# Keyboard.net
KiCad netlist of a schematic drawn in EAGLE
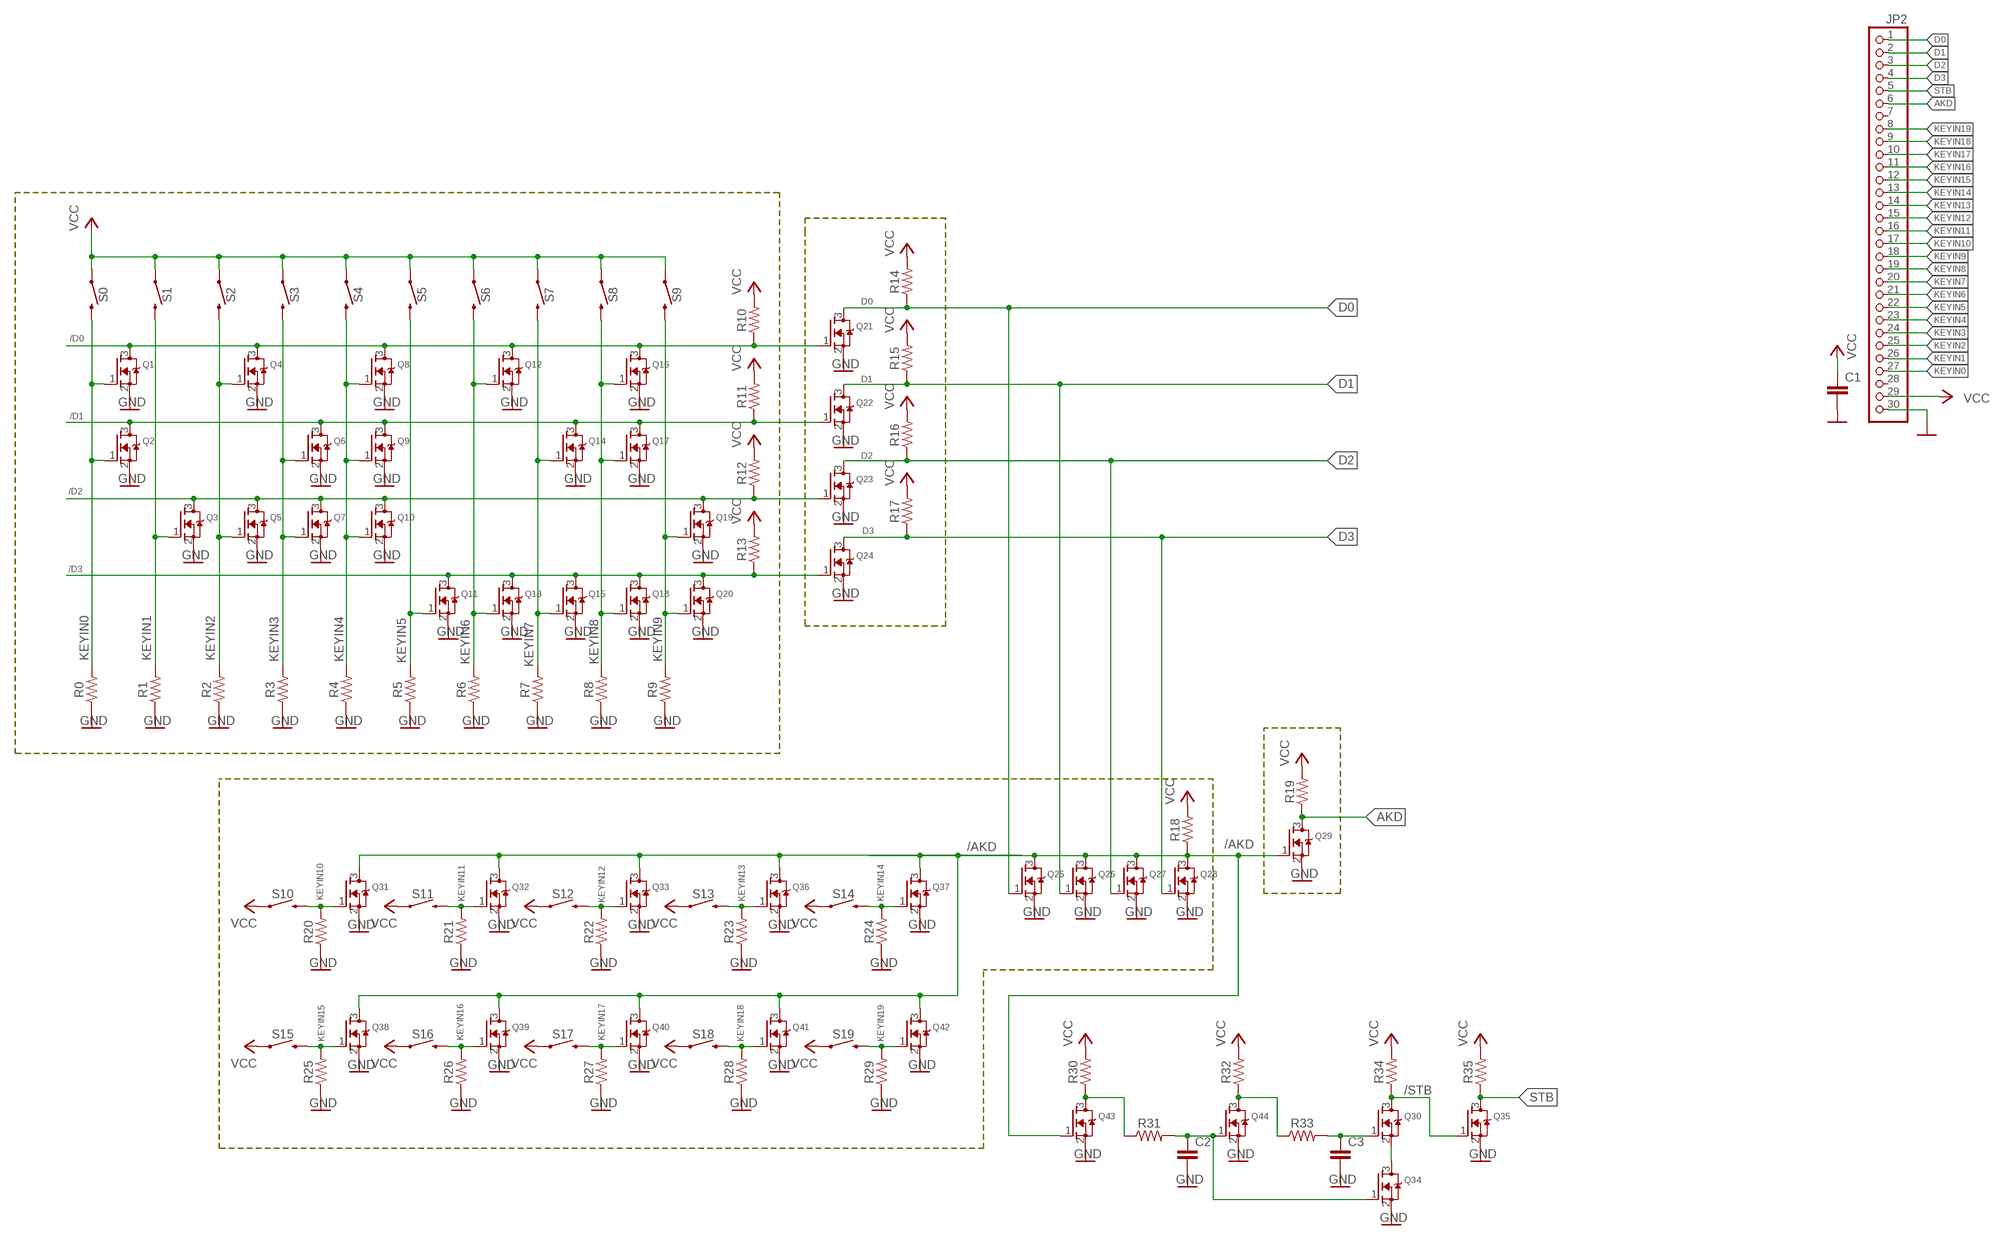
[diagram p0: schematic, sheet 1]

(export (version "E")
  (design (tool "Eeschema 10.0.6"))
  (components
    (comp (ref "C1")
      (value "C-EUC0805K")
      (footprint "eagle-import:C0805K")
      (libsource (lib "eagle-import") (part "C-EUC0805K"))
    )
    (comp (ref "C2")
      (value "C-EUC0805K")
      (footprint "eagle-import:C0805K")
      (libsource (lib "eagle-import") (part "C-EUC0805K"))
    )
    (comp (ref "C3")
      (value "C-EUC0805K")
      (footprint "eagle-import:C0805K")
      (libsource (lib "eagle-import") (part "C-EUC0805K"))
    )
    (comp (ref "JP2")
      (value "PINHD-1X30")
      (footprint "eagle-import:1X30")
      (libsource (lib "eagle-import") (part "PINHD-1X30"))
    )
    (comp (ref "Q1")
      (value "NMOSREFLOW")
      (footprint "eagle-import:SOT23")
      (libsource (lib "eagle-import") (part "NMOSREFLOW"))
    )
    (comp (ref "Q2")
      (value "NMOSREFLOW")
      (footprint "eagle-import:SOT23")
      (libsource (lib "eagle-import") (part "NMOSREFLOW"))
    )
    (comp (ref "Q3")
      (value "NMOSREFLOW")
      (footprint "eagle-import:SOT23")
      (libsource (lib "eagle-import") (part "NMOSREFLOW"))
    )
    (comp (ref "Q4")
      (value "NMOSREFLOW")
      (footprint "eagle-import:SOT23")
      (libsource (lib "eagle-import") (part "NMOSREFLOW"))
    )
    (comp (ref "Q5")
      (value "NMOSREFLOW")
      (footprint "eagle-import:SOT23")
      (libsource (lib "eagle-import") (part "NMOSREFLOW"))
    )
    (comp (ref "Q6")
      (value "NMOSREFLOW")
      (footprint "eagle-import:SOT23")
      (libsource (lib "eagle-import") (part "NMOSREFLOW"))
    )
    (comp (ref "Q7")
      (value "NMOSREFLOW")
      (footprint "eagle-import:SOT23")
      (libsource (lib "eagle-import") (part "NMOSREFLOW"))
    )
    (comp (ref "Q8")
      (value "NMOSREFLOW")
      (footprint "eagle-import:SOT23")
      (libsource (lib "eagle-import") (part "NMOSREFLOW"))
    )
    (comp (ref "Q9")
      (value "NMOSREFLOW")
      (footprint "eagle-import:SOT23")
      (libsource (lib "eagle-import") (part "NMOSREFLOW"))
    )
    (comp (ref "Q10")
      (value "NMOSREFLOW")
      (footprint "eagle-import:SOT23")
      (libsource (lib "eagle-import") (part "NMOSREFLOW"))
    )
    (comp (ref "Q11")
      (value "NMOSREFLOW")
      (footprint "eagle-import:SOT23")
      (libsource (lib "eagle-import") (part "NMOSREFLOW"))
    )
    (comp (ref "Q12")
      (value "NMOSREFLOW")
      (footprint "eagle-import:SOT23")
      (libsource (lib "eagle-import") (part "NMOSREFLOW"))
    )
    (comp (ref "Q13")
      (value "NMOSREFLOW")
      (footprint "eagle-import:SOT23")
      (libsource (lib "eagle-import") (part "NMOSREFLOW"))
    )
    (comp (ref "Q14")
      (value "NMOSREFLOW")
      (footprint "eagle-import:SOT23")
      (libsource (lib "eagle-import") (part "NMOSREFLOW"))
    )
    (comp (ref "Q15")
      (value "NMOSREFLOW")
      (footprint "eagle-import:SOT23")
      (libsource (lib "eagle-import") (part "NMOSREFLOW"))
    )
    (comp (ref "Q16")
      (value "NMOSREFLOW")
      (footprint "eagle-import:SOT23")
      (libsource (lib "eagle-import") (part "NMOSREFLOW"))
    )
    (comp (ref "Q17")
      (value "NMOSREFLOW")
      (footprint "eagle-import:SOT23")
      (libsource (lib "eagle-import") (part "NMOSREFLOW"))
    )
    (comp (ref "Q18")
      (value "NMOSREFLOW")
      (footprint "eagle-import:SOT23")
      (libsource (lib "eagle-import") (part "NMOSREFLOW"))
    )
    (comp (ref "Q19")
      (value "NMOSREFLOW")
      (footprint "eagle-import:SOT23")
      (libsource (lib "eagle-import") (part "NMOSREFLOW"))
    )
    (comp (ref "Q20")
      (value "NMOSREFLOW")
      (footprint "eagle-import:SOT23")
      (libsource (lib "eagle-import") (part "NMOSREFLOW"))
    )
    (comp (ref "Q21")
      (value "NMOSREFLOW")
      (footprint "eagle-import:SOT23")
      (libsource (lib "eagle-import") (part "NMOSREFLOW"))
    )
    (comp (ref "Q22")
      (value "NMOSREFLOW")
      (footprint "eagle-import:SOT23")
      (libsource (lib "eagle-import") (part "NMOSREFLOW"))
    )
    (comp (ref "Q23")
      (value "NMOSREFLOW")
      (footprint "eagle-import:SOT23")
      (libsource (lib "eagle-import") (part "NMOSREFLOW"))
    )
    (comp (ref "Q24")
      (value "NMOSREFLOW")
      (footprint "eagle-import:SOT23")
      (libsource (lib "eagle-import") (part "NMOSREFLOW"))
    )
    (comp (ref "Q25")
      (value "NMOSREFLOW")
      (footprint "eagle-import:SOT23")
      (libsource (lib "eagle-import") (part "NMOSREFLOW"))
    )
    (comp (ref "Q26")
      (value "NMOSREFLOW")
      (footprint "eagle-import:SOT23")
      (libsource (lib "eagle-import") (part "NMOSREFLOW"))
    )
    (comp (ref "Q27")
      (value "NMOSREFLOW")
      (footprint "eagle-import:SOT23")
      (libsource (lib "eagle-import") (part "NMOSREFLOW"))
    )
    (comp (ref "Q28")
      (value "NMOSREFLOW")
      (footprint "eagle-import:SOT23")
      (libsource (lib "eagle-import") (part "NMOSREFLOW"))
    )
    (comp (ref "Q29")
      (value "NMOSREFLOW")
      (footprint "eagle-import:SOT23")
      (libsource (lib "eagle-import") (part "NMOSREFLOW"))
    )
    (comp (ref "Q30")
      (value "NMOSREFLOW")
      (footprint "eagle-import:SOT23")
      (libsource (lib "eagle-import") (part "NMOSREFLOW"))
    )
    (comp (ref "Q31")
      (value "NMOSREFLOW")
      (footprint "eagle-import:SOT23")
      (libsource (lib "eagle-import") (part "NMOSREFLOW"))
    )
    (comp (ref "Q32")
      (value "NMOSREFLOW")
      (footprint "eagle-import:SOT23")
      (libsource (lib "eagle-import") (part "NMOSREFLOW"))
    )
    (comp (ref "Q33")
      (value "NMOSREFLOW")
      (footprint "eagle-import:SOT23")
      (libsource (lib "eagle-import") (part "NMOSREFLOW"))
    )
    (comp (ref "Q34")
      (value "NMOSREFLOW")
      (footprint "eagle-import:SOT23")
      (libsource (lib "eagle-import") (part "NMOSREFLOW"))
    )
    (comp (ref "Q35")
      (value "NMOSREFLOW")
      (footprint "eagle-import:SOT23")
      (libsource (lib "eagle-import") (part "NMOSREFLOW"))
    )
    (comp (ref "Q36")
      (value "NMOSREFLOW")
      (footprint "eagle-import:SOT23")
      (libsource (lib "eagle-import") (part "NMOSREFLOW"))
    )
    (comp (ref "Q37")
      (value "NMOSREFLOW")
      (footprint "eagle-import:SOT23")
      (libsource (lib "eagle-import") (part "NMOSREFLOW"))
    )
    (comp (ref "Q38")
      (value "NMOSREFLOW")
      (footprint "eagle-import:SOT23")
      (libsource (lib "eagle-import") (part "NMOSREFLOW"))
    )
    (comp (ref "Q39")
      (value "NMOSREFLOW")
      (footprint "eagle-import:SOT23")
      (libsource (lib "eagle-import") (part "NMOSREFLOW"))
    )
    (comp (ref "Q40")
      (value "NMOSREFLOW")
      (footprint "eagle-import:SOT23")
      (libsource (lib "eagle-import") (part "NMOSREFLOW"))
    )
    (comp (ref "Q41")
      (value "NMOSREFLOW")
      (footprint "eagle-import:SOT23")
      (libsource (lib "eagle-import") (part "NMOSREFLOW"))
    )
    (comp (ref "Q42")
      (value "NMOSREFLOW")
      (footprint "eagle-import:SOT23")
      (libsource (lib "eagle-import") (part "NMOSREFLOW"))
    )
    (comp (ref "Q43")
      (value "NMOSREFLOW")
      (footprint "eagle-import:SOT23")
      (libsource (lib "eagle-import") (part "NMOSREFLOW"))
    )
    (comp (ref "Q44")
      (value "NMOSREFLOW")
      (footprint "eagle-import:SOT23")
      (libsource (lib "eagle-import") (part "NMOSREFLOW"))
    )
    (comp (ref "R0")
      (value "RESISTOR0805")
      (footprint "eagle-import:0805")
      (libsource (lib "eagle-import") (part "RESISTOR0805"))
    )
    (comp (ref "R1")
      (value "RESISTOR0805")
      (footprint "eagle-import:0805")
      (libsource (lib "eagle-import") (part "RESISTOR0805"))
    )
    (comp (ref "R2")
      (value "RESISTOR0805")
      (footprint "eagle-import:0805")
      (libsource (lib "eagle-import") (part "RESISTOR0805"))
    )
    (comp (ref "R3")
      (value "RESISTOR0805")
      (footprint "eagle-import:0805")
      (libsource (lib "eagle-import") (part "RESISTOR0805"))
    )
    (comp (ref "R4")
      (value "RESISTOR0805")
      (footprint "eagle-import:0805")
      (libsource (lib "eagle-import") (part "RESISTOR0805"))
    )
    (comp (ref "R5")
      (value "RESISTOR0805")
      (footprint "eagle-import:0805")
      (libsource (lib "eagle-import") (part "RESISTOR0805"))
    )
    (comp (ref "R6")
      (value "RESISTOR0805")
      (footprint "eagle-import:0805")
      (libsource (lib "eagle-import") (part "RESISTOR0805"))
    )
    (comp (ref "R7")
      (value "RESISTOR0805")
      (footprint "eagle-import:0805")
      (libsource (lib "eagle-import") (part "RESISTOR0805"))
    )
    (comp (ref "R8")
      (value "RESISTOR0805")
      (footprint "eagle-import:0805")
      (libsource (lib "eagle-import") (part "RESISTOR0805"))
    )
    (comp (ref "R9")
      (value "RESISTOR0805")
      (footprint "eagle-import:0805")
      (libsource (lib "eagle-import") (part "RESISTOR0805"))
    )
    (comp (ref "R10")
      (value "RESISTOR0805")
      (footprint "eagle-import:0805")
      (libsource (lib "eagle-import") (part "RESISTOR0805"))
    )
    (comp (ref "R11")
      (value "RESISTOR0805")
      (footprint "eagle-import:0805")
      (libsource (lib "eagle-import") (part "RESISTOR0805"))
    )
    (comp (ref "R12")
      (value "RESISTOR0805")
      (footprint "eagle-import:0805")
      (libsource (lib "eagle-import") (part "RESISTOR0805"))
    )
    (comp (ref "R13")
      (value "RESISTOR0805")
      (footprint "eagle-import:0805")
      (libsource (lib "eagle-import") (part "RESISTOR0805"))
    )
    (comp (ref "R14")
      (value "RESISTOR0805")
      (footprint "eagle-import:0805")
      (libsource (lib "eagle-import") (part "RESISTOR0805"))
    )
    (comp (ref "R15")
      (value "RESISTOR0805")
      (footprint "eagle-import:0805")
      (libsource (lib "eagle-import") (part "RESISTOR0805"))
    )
    (comp (ref "R16")
      (value "RESISTOR0805")
      (footprint "eagle-import:0805")
      (libsource (lib "eagle-import") (part "RESISTOR0805"))
    )
    (comp (ref "R17")
      (value "RESISTOR0805")
      (footprint "eagle-import:0805")
      (libsource (lib "eagle-import") (part "RESISTOR0805"))
    )
    (comp (ref "R18")
      (value "RESISTOR0805")
      (footprint "eagle-import:0805")
      (libsource (lib "eagle-import") (part "RESISTOR0805"))
    )
    (comp (ref "R19")
      (value "RESISTOR0805")
      (footprint "eagle-import:0805")
      (libsource (lib "eagle-import") (part "RESISTOR0805"))
    )
    (comp (ref "R20")
      (value "RESISTOR0805")
      (footprint "eagle-import:0805")
      (libsource (lib "eagle-import") (part "RESISTOR0805"))
    )
    (comp (ref "R21")
      (value "RESISTOR0805")
      (footprint "eagle-import:0805")
      (libsource (lib "eagle-import") (part "RESISTOR0805"))
    )
    (comp (ref "R22")
      (value "RESISTOR0805")
      (footprint "eagle-import:0805")
      (libsource (lib "eagle-import") (part "RESISTOR0805"))
    )
    (comp (ref "R23")
      (value "RESISTOR0805")
      (footprint "eagle-import:0805")
      (libsource (lib "eagle-import") (part "RESISTOR0805"))
    )
    (comp (ref "R24")
      (value "RESISTOR0805")
      (footprint "eagle-import:0805")
      (libsource (lib "eagle-import") (part "RESISTOR0805"))
    )
    (comp (ref "R25")
      (value "RESISTOR0805")
      (footprint "eagle-import:0805")
      (libsource (lib "eagle-import") (part "RESISTOR0805"))
    )
    (comp (ref "R26")
      (value "RESISTOR0805")
      (footprint "eagle-import:0805")
      (libsource (lib "eagle-import") (part "RESISTOR0805"))
    )
    (comp (ref "R27")
      (value "RESISTOR0805")
      (footprint "eagle-import:0805")
      (libsource (lib "eagle-import") (part "RESISTOR0805"))
    )
    (comp (ref "R28")
      (value "RESISTOR0805")
      (footprint "eagle-import:0805")
      (libsource (lib "eagle-import") (part "RESISTOR0805"))
    )
    (comp (ref "R29")
      (value "RESISTOR0805")
      (footprint "eagle-import:0805")
      (libsource (lib "eagle-import") (part "RESISTOR0805"))
    )
    (comp (ref "R30")
      (value "RESISTOR0805")
      (footprint "eagle-import:0805")
      (libsource (lib "eagle-import") (part "RESISTOR0805"))
    )
    (comp (ref "R31")
      (value "RESISTOR0805")
      (footprint "eagle-import:0805")
      (libsource (lib "eagle-import") (part "RESISTOR0805"))
    )
    (comp (ref "R32")
      (value "RESISTOR0805")
      (footprint "eagle-import:0805")
      (libsource (lib "eagle-import") (part "RESISTOR0805"))
    )
    (comp (ref "R33")
      (value "RESISTOR0805")
      (footprint "eagle-import:0805")
      (libsource (lib "eagle-import") (part "RESISTOR0805"))
    )
    (comp (ref "R34")
      (value "RESISTOR0805")
      (footprint "eagle-import:0805")
      (libsource (lib "eagle-import") (part "RESISTOR0805"))
    )
    (comp (ref "R35")
      (value "RESISTOR0805")
      (footprint "eagle-import:0805")
      (libsource (lib "eagle-import") (part "RESISTOR0805"))
    )
    (comp (ref "S0")
      (value "MOMENTARY-SWITCH-SPST-PTH-6.0MM")
      (footprint "eagle-import:TACTILE_SWITCH_PTH_6.0MM")
      (libsource (lib "eagle-import") (part "MOMENTARY-SWITCH-SPST-PTH-6.0MM"))
    )
    (comp (ref "S1")
      (value "MOMENTARY-SWITCH-SPST-PTH-6.0MM")
      (footprint "eagle-import:TACTILE_SWITCH_PTH_6.0MM")
      (libsource (lib "eagle-import") (part "MOMENTARY-SWITCH-SPST-PTH-6.0MM"))
    )
    (comp (ref "S2")
      (value "MOMENTARY-SWITCH-SPST-PTH-6.0MM")
      (footprint "eagle-import:TACTILE_SWITCH_PTH_6.0MM")
      (libsource (lib "eagle-import") (part "MOMENTARY-SWITCH-SPST-PTH-6.0MM"))
    )
    (comp (ref "S3")
      (value "MOMENTARY-SWITCH-SPST-PTH-6.0MM")
      (footprint "eagle-import:TACTILE_SWITCH_PTH_6.0MM")
      (libsource (lib "eagle-import") (part "MOMENTARY-SWITCH-SPST-PTH-6.0MM"))
    )
    (comp (ref "S4")
      (value "MOMENTARY-SWITCH-SPST-PTH-6.0MM")
      (footprint "eagle-import:TACTILE_SWITCH_PTH_6.0MM")
      (libsource (lib "eagle-import") (part "MOMENTARY-SWITCH-SPST-PTH-6.0MM"))
    )
    (comp (ref "S5")
      (value "MOMENTARY-SWITCH-SPST-PTH-6.0MM")
      (footprint "eagle-import:TACTILE_SWITCH_PTH_6.0MM")
      (libsource (lib "eagle-import") (part "MOMENTARY-SWITCH-SPST-PTH-6.0MM"))
    )
    (comp (ref "S6")
      (value "MOMENTARY-SWITCH-SPST-PTH-6.0MM")
      (footprint "eagle-import:TACTILE_SWITCH_PTH_6.0MM")
      (libsource (lib "eagle-import") (part "MOMENTARY-SWITCH-SPST-PTH-6.0MM"))
    )
    (comp (ref "S7")
      (value "MOMENTARY-SWITCH-SPST-PTH-6.0MM")
      (footprint "eagle-import:TACTILE_SWITCH_PTH_6.0MM")
      (libsource (lib "eagle-import") (part "MOMENTARY-SWITCH-SPST-PTH-6.0MM"))
    )
    (comp (ref "S8")
      (value "MOMENTARY-SWITCH-SPST-PTH-6.0MM")
      (footprint "eagle-import:TACTILE_SWITCH_PTH_6.0MM")
      (libsource (lib "eagle-import") (part "MOMENTARY-SWITCH-SPST-PTH-6.0MM"))
    )
    (comp (ref "S9")
      (value "MOMENTARY-SWITCH-SPST-PTH-6.0MM")
      (footprint "eagle-import:TACTILE_SWITCH_PTH_6.0MM")
      (libsource (lib "eagle-import") (part "MOMENTARY-SWITCH-SPST-PTH-6.0MM"))
    )
    (comp (ref "S10")
      (value "MOMENTARY-SWITCH-SPST-PTH-6.0MM")
      (footprint "eagle-import:TACTILE_SWITCH_PTH_6.0MM")
      (libsource (lib "eagle-import") (part "MOMENTARY-SWITCH-SPST-PTH-6.0MM"))
    )
    (comp (ref "S11")
      (value "MOMENTARY-SWITCH-SPST-PTH-6.0MM")
      (footprint "eagle-import:TACTILE_SWITCH_PTH_6.0MM")
      (libsource (lib "eagle-import") (part "MOMENTARY-SWITCH-SPST-PTH-6.0MM"))
    )
    (comp (ref "S12")
      (value "MOMENTARY-SWITCH-SPST-PTH-6.0MM")
      (footprint "eagle-import:TACTILE_SWITCH_PTH_6.0MM")
      (libsource (lib "eagle-import") (part "MOMENTARY-SWITCH-SPST-PTH-6.0MM"))
    )
    (comp (ref "S13")
      (value "MOMENTARY-SWITCH-SPST-PTH-6.0MM")
      (footprint "eagle-import:TACTILE_SWITCH_PTH_6.0MM")
      (libsource (lib "eagle-import") (part "MOMENTARY-SWITCH-SPST-PTH-6.0MM"))
    )
    (comp (ref "S14")
      (value "MOMENTARY-SWITCH-SPST-PTH-6.0MM")
      (footprint "eagle-import:TACTILE_SWITCH_PTH_6.0MM")
      (libsource (lib "eagle-import") (part "MOMENTARY-SWITCH-SPST-PTH-6.0MM"))
    )
    (comp (ref "S15")
      (value "MOMENTARY-SWITCH-SPST-PTH-6.0MM")
      (footprint "eagle-import:TACTILE_SWITCH_PTH_6.0MM")
      (libsource (lib "eagle-import") (part "MOMENTARY-SWITCH-SPST-PTH-6.0MM"))
    )
    (comp (ref "S16")
      (value "MOMENTARY-SWITCH-SPST-PTH-6.0MM")
      (footprint "eagle-import:TACTILE_SWITCH_PTH_6.0MM")
      (libsource (lib "eagle-import") (part "MOMENTARY-SWITCH-SPST-PTH-6.0MM"))
    )
    (comp (ref "S17")
      (value "MOMENTARY-SWITCH-SPST-PTH-6.0MM")
      (footprint "eagle-import:TACTILE_SWITCH_PTH_6.0MM")
      (libsource (lib "eagle-import") (part "MOMENTARY-SWITCH-SPST-PTH-6.0MM"))
    )
    (comp (ref "S18")
      (value "MOMENTARY-SWITCH-SPST-PTH-6.0MM")
      (footprint "eagle-import:TACTILE_SWITCH_PTH_6.0MM")
      (libsource (lib "eagle-import") (part "MOMENTARY-SWITCH-SPST-PTH-6.0MM"))
    )
    (comp (ref "S19")
      (value "MOMENTARY-SWITCH-SPST-PTH-6.0MM")
      (footprint "eagle-import:TACTILE_SWITCH_PTH_6.0MM")
      (libsource (lib "eagle-import") (part "MOMENTARY-SWITCH-SPST-PTH-6.0MM"))
    )
  )
  (nets
    (net (code "1") (name "/{slash}AKD") (class "Default")
      (node (ref "Q25") (pin "3") (pinfunction "D_3") (pintype "bidirectional"))
      (node (ref "Q26") (pin "3") (pinfunction "D_3") (pintype "bidirectional"))
      (node (ref "Q27") (pin "3") (pinfunction "D_3") (pintype "bidirectional"))
      (node (ref "Q28") (pin "3") (pinfunction "D_3") (pintype "bidirectional"))
      (node (ref "Q29") (pin "1") (pinfunction "G_1") (pintype "bidirectional"))
      (node (ref "Q31") (pin "3") (pinfunction "D_3") (pintype "bidirectional"))
      (node (ref "Q32") (pin "3") (pinfunction "D_3") (pintype "bidirectional"))
      (node (ref "Q33") (pin "3") (pinfunction "D_3") (pintype "bidirectional"))
      (node (ref "Q36") (pin "3") (pinfunction "D_3") (pintype "bidirectional"))
      (node (ref "Q37") (pin "3") (pinfunction "D_3") (pintype "bidirectional"))
      (node (ref "Q38") (pin "3") (pinfunction "D_3") (pintype "bidirectional"))
      (node (ref "Q39") (pin "3") (pinfunction "D_3") (pintype "bidirectional"))
      (node (ref "Q40") (pin "3") (pinfunction "D_3") (pintype "bidirectional"))
      (node (ref "Q41") (pin "3") (pinfunction "D_3") (pintype "bidirectional"))
      (node (ref "Q42") (pin "3") (pinfunction "D_3") (pintype "bidirectional"))
      (node (ref "Q43") (pin "1") (pinfunction "G_1") (pintype "bidirectional"))
      (node (ref "R18") (pin "1") (pinfunction "1_1") (pintype "passive"))
    )
    (net (code "2") (name "/{slash}D0") (class "Default")
      (node (ref "Q1") (pin "3") (pinfunction "D_3") (pintype "bidirectional"))
      (node (ref "Q12") (pin "3") (pinfunction "D_3") (pintype "bidirectional"))
      (node (ref "Q16") (pin "3") (pinfunction "D_3") (pintype "bidirectional"))
      (node (ref "Q21") (pin "1") (pinfunction "G_1") (pintype "bidirectional"))
      (node (ref "Q4") (pin "3") (pinfunction "D_3") (pintype "bidirectional"))
      (node (ref "Q8") (pin "3") (pinfunction "D_3") (pintype "bidirectional"))
      (node (ref "R10") (pin "1") (pinfunction "1_1") (pintype "passive"))
    )
    (net (code "3") (name "/{slash}D1") (class "Default")
      (node (ref "Q14") (pin "3") (pinfunction "D_3") (pintype "bidirectional"))
      (node (ref "Q17") (pin "3") (pinfunction "D_3") (pintype "bidirectional"))
      (node (ref "Q2") (pin "3") (pinfunction "D_3") (pintype "bidirectional"))
      (node (ref "Q22") (pin "1") (pinfunction "G_1") (pintype "bidirectional"))
      (node (ref "Q6") (pin "3") (pinfunction "D_3") (pintype "bidirectional"))
      (node (ref "Q9") (pin "3") (pinfunction "D_3") (pintype "bidirectional"))
      (node (ref "R11") (pin "1") (pinfunction "1_1") (pintype "passive"))
    )
    (net (code "4") (name "/{slash}D2") (class "Default")
      (node (ref "Q10") (pin "3") (pinfunction "D_3") (pintype "bidirectional"))
      (node (ref "Q19") (pin "3") (pinfunction "D_3") (pintype "bidirectional"))
      (node (ref "Q23") (pin "1") (pinfunction "G_1") (pintype "bidirectional"))
      (node (ref "Q3") (pin "3") (pinfunction "D_3") (pintype "bidirectional"))
      (node (ref "Q5") (pin "3") (pinfunction "D_3") (pintype "bidirectional"))
      (node (ref "Q7") (pin "3") (pinfunction "D_3") (pintype "bidirectional"))
      (node (ref "R12") (pin "1") (pinfunction "1_1") (pintype "passive"))
    )
    (net (code "5") (name "/{slash}D3") (class "Default")
      (node (ref "Q11") (pin "3") (pinfunction "D_3") (pintype "bidirectional"))
      (node (ref "Q13") (pin "3") (pinfunction "D_3") (pintype "bidirectional"))
      (node (ref "Q15") (pin "3") (pinfunction "D_3") (pintype "bidirectional"))
      (node (ref "Q18") (pin "3") (pinfunction "D_3") (pintype "bidirectional"))
      (node (ref "Q20") (pin "3") (pinfunction "D_3") (pintype "bidirectional"))
      (node (ref "Q24") (pin "1") (pinfunction "G_1") (pintype "bidirectional"))
      (node (ref "R13") (pin "1") (pinfunction "1_1") (pintype "passive"))
    )
    (net (code "6") (name "/{slash}STB") (class "Default")
      (node (ref "Q30") (pin "3") (pinfunction "D_3") (pintype "bidirectional"))
      (node (ref "Q35") (pin "1") (pinfunction "G_1") (pintype "bidirectional"))
      (node (ref "R34") (pin "1") (pinfunction "1_1") (pintype "passive"))
    )
    (net (code "7") (name "AKD") (class "Default")
      (node (ref "JP2") (pin "6") (pinfunction "6_6") (pintype "passive"))
      (node (ref "Q29") (pin "3") (pinfunction "D_3") (pintype "bidirectional"))
      (node (ref "R19") (pin "1") (pinfunction "1_1") (pintype "passive"))
    )
    (net (code "8") (name "D0") (class "Default")
      (node (ref "JP2") (pin "1") (pinfunction "1_1") (pintype "passive"))
      (node (ref "Q21") (pin "3") (pinfunction "D_3") (pintype "bidirectional"))
      (node (ref "Q25") (pin "1") (pinfunction "G_1") (pintype "bidirectional"))
      (node (ref "R14") (pin "1") (pinfunction "1_1") (pintype "passive"))
    )
    (net (code "9") (name "D1") (class "Default")
      (node (ref "JP2") (pin "2") (pinfunction "2_2") (pintype "passive"))
      (node (ref "Q22") (pin "3") (pinfunction "D_3") (pintype "bidirectional"))
      (node (ref "Q26") (pin "1") (pinfunction "G_1") (pintype "bidirectional"))
      (node (ref "R15") (pin "1") (pinfunction "1_1") (pintype "passive"))
    )
    (net (code "10") (name "D2") (class "Default")
      (node (ref "JP2") (pin "3") (pinfunction "3_3") (pintype "passive"))
      (node (ref "Q23") (pin "3") (pinfunction "D_3") (pintype "bidirectional"))
      (node (ref "Q27") (pin "1") (pinfunction "G_1") (pintype "bidirectional"))
      (node (ref "R16") (pin "1") (pinfunction "1_1") (pintype "passive"))
    )
    (net (code "11") (name "D3") (class "Default")
      (node (ref "JP2") (pin "4") (pinfunction "4_4") (pintype "passive"))
      (node (ref "Q24") (pin "3") (pinfunction "D_3") (pintype "bidirectional"))
      (node (ref "Q28") (pin "1") (pinfunction "G_1") (pintype "bidirectional"))
      (node (ref "R17") (pin "1") (pinfunction "1_1") (pintype "passive"))
    )
    (net (code "12") (name "GND") (class "Default")
      (node (ref "C1") (pin "2") (pinfunction "2_2") (pintype "passive"))
      (node (ref "C2") (pin "2") (pinfunction "2_2") (pintype "passive"))
      (node (ref "C3") (pin "2") (pinfunction "2_2") (pintype "passive"))
      (node (ref "JP2") (pin "30") (pinfunction "30_30") (pintype "passive"))
      (node (ref "Q1") (pin "2") (pinfunction "S_2") (pintype "bidirectional"))
      (node (ref "Q10") (pin "2") (pinfunction "S_2") (pintype "bidirectional"))
      (node (ref "Q11") (pin "2") (pinfunction "S_2") (pintype "bidirectional"))
      (node (ref "Q12") (pin "2") (pinfunction "S_2") (pintype "bidirectional"))
      (node (ref "Q13") (pin "2") (pinfunction "S_2") (pintype "bidirectional"))
      (node (ref "Q14") (pin "2") (pinfunction "S_2") (pintype "bidirectional"))
      (node (ref "Q15") (pin "2") (pinfunction "S_2") (pintype "bidirectional"))
      (node (ref "Q16") (pin "2") (pinfunction "S_2") (pintype "bidirectional"))
      (node (ref "Q17") (pin "2") (pinfunction "S_2") (pintype "bidirectional"))
      (node (ref "Q18") (pin "2") (pinfunction "S_2") (pintype "bidirectional"))
      (node (ref "Q19") (pin "2") (pinfunction "S_2") (pintype "bidirectional"))
      (node (ref "Q2") (pin "2") (pinfunction "S_2") (pintype "bidirectional"))
      (node (ref "Q20") (pin "2") (pinfunction "S_2") (pintype "bidirectional"))
      (node (ref "Q21") (pin "2") (pinfunction "S_2") (pintype "bidirectional"))
      (node (ref "Q22") (pin "2") (pinfunction "S_2") (pintype "bidirectional"))
      (node (ref "Q23") (pin "2") (pinfunction "S_2") (pintype "bidirectional"))
      (node (ref "Q24") (pin "2") (pinfunction "S_2") (pintype "bidirectional"))
      (node (ref "Q25") (pin "2") (pinfunction "S_2") (pintype "bidirectional"))
      (node (ref "Q26") (pin "2") (pinfunction "S_2") (pintype "bidirectional"))
      (node (ref "Q27") (pin "2") (pinfunction "S_2") (pintype "bidirectional"))
      (node (ref "Q28") (pin "2") (pinfunction "S_2") (pintype "bidirectional"))
      (node (ref "Q29") (pin "2") (pinfunction "S_2") (pintype "bidirectional"))
      (node (ref "Q3") (pin "2") (pinfunction "S_2") (pintype "bidirectional"))
      (node (ref "Q31") (pin "2") (pinfunction "S_2") (pintype "bidirectional"))
      (node (ref "Q32") (pin "2") (pinfunction "S_2") (pintype "bidirectional"))
      (node (ref "Q33") (pin "2") (pinfunction "S_2") (pintype "bidirectional"))
      (node (ref "Q34") (pin "2") (pinfunction "S_2") (pintype "bidirectional"))
      (node (ref "Q35") (pin "2") (pinfunction "S_2") (pintype "bidirectional"))
      (node (ref "Q36") (pin "2") (pinfunction "S_2") (pintype "bidirectional"))
      (node (ref "Q37") (pin "2") (pinfunction "S_2") (pintype "bidirectional"))
      (node (ref "Q38") (pin "2") (pinfunction "S_2") (pintype "bidirectional"))
      (node (ref "Q39") (pin "2") (pinfunction "S_2") (pintype "bidirectional"))
      (node (ref "Q4") (pin "2") (pinfunction "S_2") (pintype "bidirectional"))
      (node (ref "Q40") (pin "2") (pinfunction "S_2") (pintype "bidirectional"))
      (node (ref "Q41") (pin "2") (pinfunction "S_2") (pintype "bidirectional"))
      (node (ref "Q42") (pin "2") (pinfunction "S_2") (pintype "bidirectional"))
      (node (ref "Q43") (pin "2") (pinfunction "S_2") (pintype "bidirectional"))
      (node (ref "Q44") (pin "2") (pinfunction "S_2") (pintype "bidirectional"))
      (node (ref "Q5") (pin "2") (pinfunction "S_2") (pintype "bidirectional"))
      (node (ref "Q6") (pin "2") (pinfunction "S_2") (pintype "bidirectional"))
      (node (ref "Q7") (pin "2") (pinfunction "S_2") (pintype "bidirectional"))
      (node (ref "Q8") (pin "2") (pinfunction "S_2") (pintype "bidirectional"))
      (node (ref "Q9") (pin "2") (pinfunction "S_2") (pintype "bidirectional"))
      (node (ref "R0") (pin "1") (pinfunction "1_1") (pintype "passive"))
      (node (ref "R1") (pin "1") (pinfunction "1_1") (pintype "passive"))
      (node (ref "R2") (pin "1") (pinfunction "1_1") (pintype "passive"))
      (node (ref "R20") (pin "1") (pinfunction "1_1") (pintype "passive"))
      (node (ref "R21") (pin "1") (pinfunction "1_1") (pintype "passive"))
      (node (ref "R22") (pin "1") (pinfunction "1_1") (pintype "passive"))
      (node (ref "R23") (pin "1") (pinfunction "1_1") (pintype "passive"))
      (node (ref "R24") (pin "1") (pinfunction "1_1") (pintype "passive"))
      (node (ref "R25") (pin "1") (pinfunction "1_1") (pintype "passive"))
      (node (ref "R26") (pin "1") (pinfunction "1_1") (pintype "passive"))
      (node (ref "R27") (pin "1") (pinfunction "1_1") (pintype "passive"))
      (node (ref "R28") (pin "1") (pinfunction "1_1") (pintype "passive"))
      (node (ref "R29") (pin "1") (pinfunction "1_1") (pintype "passive"))
      (node (ref "R3") (pin "1") (pinfunction "1_1") (pintype "passive"))
      (node (ref "R4") (pin "1") (pinfunction "1_1") (pintype "passive"))
      (node (ref "R5") (pin "1") (pinfunction "1_1") (pintype "passive"))
      (node (ref "R6") (pin "1") (pinfunction "1_1") (pintype "passive"))
      (node (ref "R7") (pin "1") (pinfunction "1_1") (pintype "passive"))
      (node (ref "R8") (pin "1") (pinfunction "1_1") (pintype "passive"))
      (node (ref "R9") (pin "1") (pinfunction "1_1") (pintype "passive"))
    )
    (net (code "13") (name "KEYIN0") (class "Default")
      (node (ref "JP2") (pin "27") (pinfunction "27_27") (pintype "passive"))
      (node (ref "Q1") (pin "1") (pinfunction "G_1") (pintype "bidirectional"))
      (node (ref "Q2") (pin "1") (pinfunction "G_1") (pintype "bidirectional"))
      (node (ref "R0") (pin "2") (pinfunction "2_2") (pintype "passive"))
      (node (ref "S0") (pin "3") (pinfunction "2_3") (pintype "passive"))
    )
    (net (code "14") (name "KEYIN1") (class "Default")
      (node (ref "JP2") (pin "26") (pinfunction "26_26") (pintype "passive"))
      (node (ref "Q3") (pin "1") (pinfunction "G_1") (pintype "bidirectional"))
      (node (ref "R1") (pin "2") (pinfunction "2_2") (pintype "passive"))
      (node (ref "S1") (pin "3") (pinfunction "2_3") (pintype "passive"))
    )
    (net (code "15") (name "KEYIN2") (class "Default")
      (node (ref "JP2") (pin "25") (pinfunction "25_25") (pintype "passive"))
      (node (ref "Q4") (pin "1") (pinfunction "G_1") (pintype "bidirectional"))
      (node (ref "Q5") (pin "1") (pinfunction "G_1") (pintype "bidirectional"))
      (node (ref "R2") (pin "2") (pinfunction "2_2") (pintype "passive"))
      (node (ref "S2") (pin "3") (pinfunction "2_3") (pintype "passive"))
    )
    (net (code "16") (name "KEYIN3") (class "Default")
      (node (ref "JP2") (pin "24") (pinfunction "24_24") (pintype "passive"))
      (node (ref "Q6") (pin "1") (pinfunction "G_1") (pintype "bidirectional"))
      (node (ref "Q7") (pin "1") (pinfunction "G_1") (pintype "bidirectional"))
      (node (ref "R3") (pin "2") (pinfunction "2_2") (pintype "passive"))
      (node (ref "S3") (pin "3") (pinfunction "2_3") (pintype "passive"))
    )
    (net (code "17") (name "KEYIN4") (class "Default")
      (node (ref "JP2") (pin "23") (pinfunction "23_23") (pintype "passive"))
      (node (ref "Q10") (pin "1") (pinfunction "G_1") (pintype "bidirectional"))
      (node (ref "Q8") (pin "1") (pinfunction "G_1") (pintype "bidirectional"))
      (node (ref "Q9") (pin "1") (pinfunction "G_1") (pintype "bidirectional"))
      (node (ref "R4") (pin "2") (pinfunction "2_2") (pintype "passive"))
      (node (ref "S4") (pin "3") (pinfunction "2_3") (pintype "passive"))
    )
    (net (code "18") (name "KEYIN5") (class "Default")
      (node (ref "JP2") (pin "22") (pinfunction "22_22") (pintype "passive"))
      (node (ref "Q11") (pin "1") (pinfunction "G_1") (pintype "bidirectional"))
      (node (ref "R5") (pin "2") (pinfunction "2_2") (pintype "passive"))
      (node (ref "S5") (pin "3") (pinfunction "2_3") (pintype "passive"))
    )
    (net (code "19") (name "KEYIN6") (class "Default")
      (node (ref "JP2") (pin "21") (pinfunction "21_21") (pintype "passive"))
      (node (ref "Q12") (pin "1") (pinfunction "G_1") (pintype "bidirectional"))
      (node (ref "Q13") (pin "1") (pinfunction "G_1") (pintype "bidirectional"))
      (node (ref "R6") (pin "2") (pinfunction "2_2") (pintype "passive"))
      (node (ref "S6") (pin "3") (pinfunction "2_3") (pintype "passive"))
    )
    (net (code "20") (name "KEYIN7") (class "Default")
      (node (ref "JP2") (pin "20") (pinfunction "20_20") (pintype "passive"))
      (node (ref "Q14") (pin "1") (pinfunction "G_1") (pintype "bidirectional"))
      (node (ref "Q15") (pin "1") (pinfunction "G_1") (pintype "bidirectional"))
      (node (ref "R7") (pin "2") (pinfunction "2_2") (pintype "passive"))
      (node (ref "S7") (pin "3") (pinfunction "2_3") (pintype "passive"))
    )
    (net (code "21") (name "KEYIN8") (class "Default")
      (node (ref "JP2") (pin "19") (pinfunction "19_19") (pintype "passive"))
      (node (ref "Q16") (pin "1") (pinfunction "G_1") (pintype "bidirectional"))
      (node (ref "Q17") (pin "1") (pinfunction "G_1") (pintype "bidirectional"))
      (node (ref "Q18") (pin "1") (pinfunction "G_1") (pintype "bidirectional"))
      (node (ref "R8") (pin "2") (pinfunction "2_2") (pintype "passive"))
      (node (ref "S8") (pin "3") (pinfunction "2_3") (pintype "passive"))
    )
    (net (code "22") (name "KEYIN9") (class "Default")
      (node (ref "JP2") (pin "18") (pinfunction "18_18") (pintype "passive"))
      (node (ref "Q19") (pin "1") (pinfunction "G_1") (pintype "bidirectional"))
      (node (ref "Q20") (pin "1") (pinfunction "G_1") (pintype "bidirectional"))
      (node (ref "R9") (pin "2") (pinfunction "2_2") (pintype "passive"))
      (node (ref "S9") (pin "3") (pinfunction "2_3") (pintype "passive"))
    )
    (net (code "23") (name "KEYIN10") (class "Default")
      (node (ref "JP2") (pin "17") (pinfunction "17_17") (pintype "passive"))
      (node (ref "Q31") (pin "1") (pinfunction "G_1") (pintype "bidirectional"))
      (node (ref "R20") (pin "2") (pinfunction "2_2") (pintype "passive"))
      (node (ref "S10") (pin "3") (pinfunction "2_3") (pintype "passive"))
    )
    (net (code "24") (name "KEYIN11") (class "Default")
      (node (ref "JP2") (pin "16") (pinfunction "16_16") (pintype "passive"))
      (node (ref "Q32") (pin "1") (pinfunction "G_1") (pintype "bidirectional"))
      (node (ref "R21") (pin "2") (pinfunction "2_2") (pintype "passive"))
      (node (ref "S11") (pin "3") (pinfunction "2_3") (pintype "passive"))
    )
    (net (code "25") (name "KEYIN12") (class "Default")
      (node (ref "JP2") (pin "15") (pinfunction "15_15") (pintype "passive"))
      (node (ref "Q33") (pin "1") (pinfunction "G_1") (pintype "bidirectional"))
      (node (ref "R22") (pin "2") (pinfunction "2_2") (pintype "passive"))
      (node (ref "S12") (pin "3") (pinfunction "2_3") (pintype "passive"))
    )
    (net (code "26") (name "KEYIN13") (class "Default")
      (node (ref "JP2") (pin "14") (pinfunction "14_14") (pintype "passive"))
      (node (ref "Q36") (pin "1") (pinfunction "G_1") (pintype "bidirectional"))
      (node (ref "R23") (pin "2") (pinfunction "2_2") (pintype "passive"))
      (node (ref "S13") (pin "3") (pinfunction "2_3") (pintype "passive"))
    )
    (net (code "27") (name "KEYIN14") (class "Default")
      (node (ref "JP2") (pin "13") (pinfunction "13_13") (pintype "passive"))
      (node (ref "Q37") (pin "1") (pinfunction "G_1") (pintype "bidirectional"))
      (node (ref "R24") (pin "2") (pinfunction "2_2") (pintype "passive"))
      (node (ref "S14") (pin "3") (pinfunction "2_3") (pintype "passive"))
    )
    (net (code "28") (name "KEYIN15") (class "Default")
      (node (ref "JP2") (pin "12") (pinfunction "12_12") (pintype "passive"))
      (node (ref "Q38") (pin "1") (pinfunction "G_1") (pintype "bidirectional"))
      (node (ref "R25") (pin "2") (pinfunction "2_2") (pintype "passive"))
      (node (ref "S15") (pin "3") (pinfunction "2_3") (pintype "passive"))
    )
    (net (code "29") (name "KEYIN16") (class "Default")
      (node (ref "JP2") (pin "11") (pinfunction "11_11") (pintype "passive"))
      (node (ref "Q39") (pin "1") (pinfunction "G_1") (pintype "bidirectional"))
      (node (ref "R26") (pin "2") (pinfunction "2_2") (pintype "passive"))
      (node (ref "S16") (pin "3") (pinfunction "2_3") (pintype "passive"))
    )
    (net (code "30") (name "KEYIN17") (class "Default")
      (node (ref "JP2") (pin "10") (pinfunction "10_10") (pintype "passive"))
      (node (ref "Q40") (pin "1") (pinfunction "G_1") (pintype "bidirectional"))
      (node (ref "R27") (pin "2") (pinfunction "2_2") (pintype "passive"))
      (node (ref "S17") (pin "3") (pinfunction "2_3") (pintype "passive"))
    )
    (net (code "31") (name "KEYIN18") (class "Default")
      (node (ref "JP2") (pin "9") (pinfunction "9_9") (pintype "passive"))
      (node (ref "Q41") (pin "1") (pinfunction "G_1") (pintype "bidirectional"))
      (node (ref "R28") (pin "2") (pinfunction "2_2") (pintype "passive"))
      (node (ref "S18") (pin "3") (pinfunction "2_3") (pintype "passive"))
    )
    (net (code "32") (name "KEYIN19") (class "Default")
      (node (ref "JP2") (pin "8") (pinfunction "8_8") (pintype "passive"))
      (node (ref "Q42") (pin "1") (pinfunction "G_1") (pintype "bidirectional"))
      (node (ref "R29") (pin "2") (pinfunction "2_2") (pintype "passive"))
      (node (ref "S19") (pin "3") (pinfunction "2_3") (pintype "passive"))
    )
    (net (code "33") (name "Net-(Q30-G)") (class "Default")
      (node (ref "C3") (pin "1") (pinfunction "1_1") (pintype "passive"))
      (node (ref "Q30") (pin "1") (pinfunction "G_1") (pintype "bidirectional"))
      (node (ref "R33") (pin "2") (pinfunction "2_2") (pintype "passive"))
    )
    (net (code "34") (name "Net-(Q30-S)") (class "Default")
      (node (ref "Q30") (pin "2") (pinfunction "S_2") (pintype "bidirectional"))
      (node (ref "Q34") (pin "3") (pinfunction "D_3") (pintype "bidirectional"))
    )
    (net (code "35") (name "Net-(Q34-G)") (class "Default")
      (node (ref "C2") (pin "1") (pinfunction "1_1") (pintype "passive"))
      (node (ref "Q34") (pin "1") (pinfunction "G_1") (pintype "bidirectional"))
      (node (ref "Q44") (pin "1") (pinfunction "G_1") (pintype "bidirectional"))
      (node (ref "R31") (pin "2") (pinfunction "2_2") (pintype "passive"))
    )
    (net (code "36") (name "Net-(Q43-D)") (class "Default")
      (node (ref "Q43") (pin "3") (pinfunction "D_3") (pintype "bidirectional"))
      (node (ref "R30") (pin "1") (pinfunction "1_1") (pintype "passive"))
      (node (ref "R31") (pin "1") (pinfunction "1_1") (pintype "passive"))
    )
    (net (code "37") (name "Net-(Q44-D)") (class "Default")
      (node (ref "Q44") (pin "3") (pinfunction "D_3") (pintype "bidirectional"))
      (node (ref "R32") (pin "1") (pinfunction "1_1") (pintype "passive"))
      (node (ref "R33") (pin "1") (pinfunction "1_1") (pintype "passive"))
    )
    (net (code "38") (name "STB") (class "Default")
      (node (ref "JP2") (pin "5") (pinfunction "5_5") (pintype "passive"))
      (node (ref "Q35") (pin "3") (pinfunction "D_3") (pintype "bidirectional"))
      (node (ref "R35") (pin "1") (pinfunction "1_1") (pintype "passive"))
    )
    (net (code "39") (name "VCC") (class "Default")
      (node (ref "C1") (pin "1") (pinfunction "1_1") (pintype "passive"))
      (node (ref "JP2") (pin "29") (pinfunction "29_29") (pintype "passive"))
      (node (ref "R10") (pin "2") (pinfunction "2_2") (pintype "passive"))
      (node (ref "R11") (pin "2") (pinfunction "2_2") (pintype "passive"))
      (node (ref "R12") (pin "2") (pinfunction "2_2") (pintype "passive"))
      (node (ref "R13") (pin "2") (pinfunction "2_2") (pintype "passive"))
      (node (ref "R14") (pin "2") (pinfunction "2_2") (pintype "passive"))
      (node (ref "R15") (pin "2") (pinfunction "2_2") (pintype "passive"))
      (node (ref "R16") (pin "2") (pinfunction "2_2") (pintype "passive"))
      (node (ref "R17") (pin "2") (pinfunction "2_2") (pintype "passive"))
      (node (ref "R18") (pin "2") (pinfunction "2_2") (pintype "passive"))
      (node (ref "R19") (pin "2") (pinfunction "2_2") (pintype "passive"))
      (node (ref "R30") (pin "2") (pinfunction "2_2") (pintype "passive"))
      (node (ref "R32") (pin "2") (pinfunction "2_2") (pintype "passive"))
      (node (ref "R34") (pin "2") (pinfunction "2_2") (pintype "passive"))
      (node (ref "R35") (pin "2") (pinfunction "2_2") (pintype "passive"))
      (node (ref "S0") (pin "1") (pinfunction "1_1") (pintype "passive"))
      (node (ref "S1") (pin "1") (pinfunction "1_1") (pintype "passive"))
      (node (ref "S10") (pin "1") (pinfunction "1_1") (pintype "passive"))
      (node (ref "S11") (pin "1") (pinfunction "1_1") (pintype "passive"))
      (node (ref "S12") (pin "1") (pinfunction "1_1") (pintype "passive"))
      (node (ref "S13") (pin "1") (pinfunction "1_1") (pintype "passive"))
      (node (ref "S14") (pin "1") (pinfunction "1_1") (pintype "passive"))
      (node (ref "S15") (pin "1") (pinfunction "1_1") (pintype "passive"))
      (node (ref "S16") (pin "1") (pinfunction "1_1") (pintype "passive"))
      (node (ref "S17") (pin "1") (pinfunction "1_1") (pintype "passive"))
      (node (ref "S18") (pin "1") (pinfunction "1_1") (pintype "passive"))
      (node (ref "S19") (pin "1") (pinfunction "1_1") (pintype "passive"))
      (node (ref "S2") (pin "1") (pinfunction "1_1") (pintype "passive"))
      (node (ref "S3") (pin "1") (pinfunction "1_1") (pintype "passive"))
      (node (ref "S4") (pin "1") (pinfunction "1_1") (pintype "passive"))
      (node (ref "S5") (pin "1") (pinfunction "1_1") (pintype "passive"))
      (node (ref "S6") (pin "1") (pinfunction "1_1") (pintype "passive"))
      (node (ref "S7") (pin "1") (pinfunction "1_1") (pintype "passive"))
      (node (ref "S8") (pin "1") (pinfunction "1_1") (pintype "passive"))
      (node (ref "S9") (pin "1") (pinfunction "1_1") (pintype "passive"))
    )
    (net (code "40") (name "unconnected-(JP2-Pad7)") (class "Default")
      (node (ref "JP2") (pin "7") (pinfunction "7_7") (pintype "passive"))
    )
    (net (code "41") (name "unconnected-(JP2-Pad28)") (class "Default")
      (node (ref "JP2") (pin "28") (pinfunction "28_28") (pintype "passive"))
    )
  )
)
